# SparkFun_SOT23-DIP-Adapter-v10.net
KiCad netlist of a schematic drawn in EAGLE
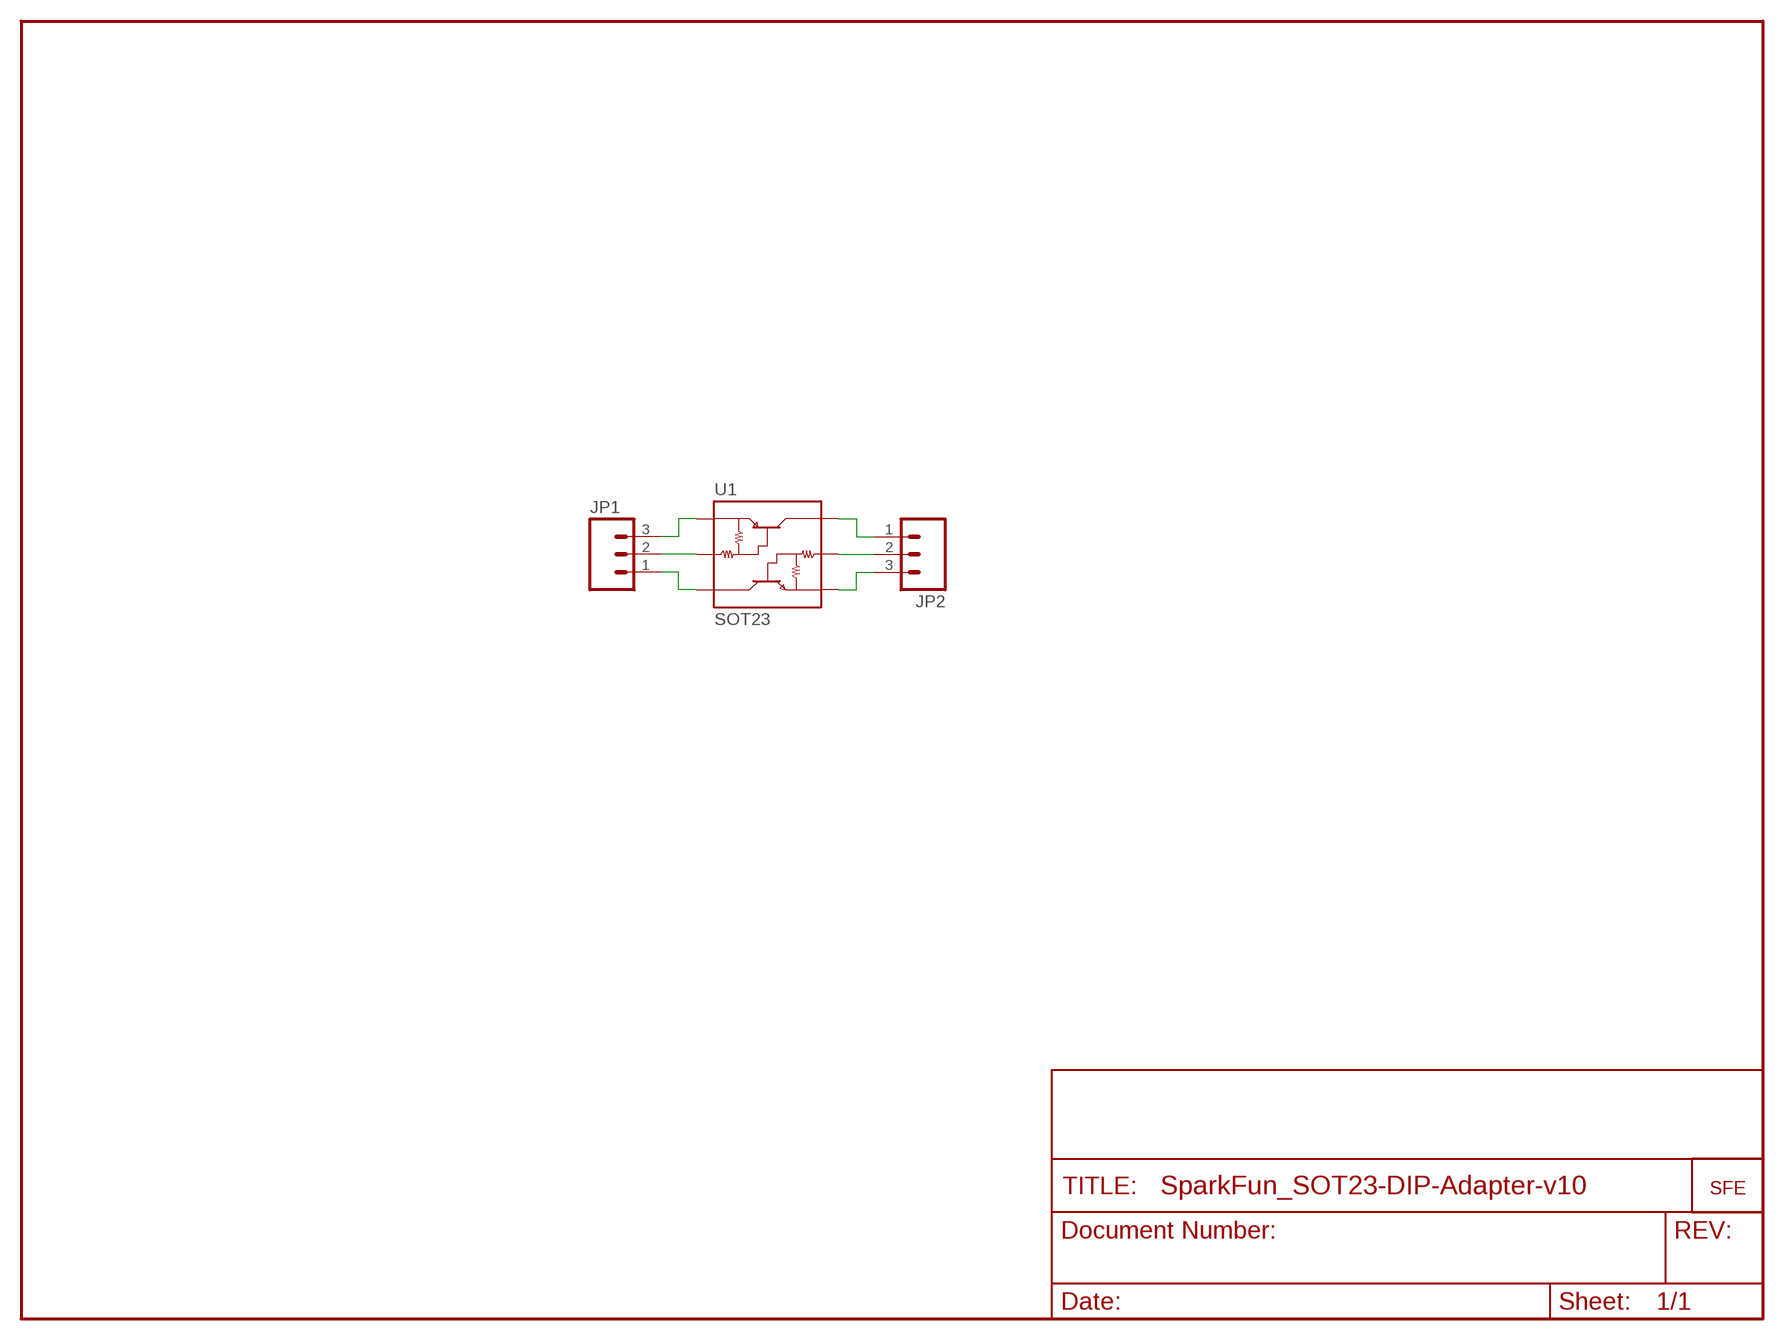
[diagram p0: schematic, sheet 1]

(export (version "E")
  (design (tool "Eeschema 10.0.6"))
  (components
    (comp (ref "JP1")
      (value "M03PTH")
      (footprint "eagle-import:1X03")
      (libsource (lib "eagle-import") (part "M03PTH"))
    )
    (comp (ref "JP2")
      (value "M03PTH")
      (footprint "eagle-import:1X03")
      (libsource (lib "eagle-import") (part "M03PTH"))
    )
    (comp (ref "U$1")
      (value "LOGO-SFESK")
      (footprint "eagle-import:SFE-LOGO-FLAME")
      (libsource (lib "eagle-import") (part "LOGO-SFESK"))
    )
    (comp (ref "U1")
      (value "SOT23")
      (footprint "eagle-import:SOT23-6")
      (libsource (lib "eagle-import") (part "XN04312SOT"))
    )
  )
  (nets
    (net (code "1") (name "Net-(U1-B1)") (class "Default")
      (node (ref "JP2") (pin "2") (pinfunction "2_2") (pintype "passive"))
      (node (ref "U1") (pin "5") (pinfunction "B1_5") (pintype "bidirectional"))
    )
    (net (code "2") (name "Net-(U1-B2)") (class "Default")
      (node (ref "JP1") (pin "2") (pinfunction "2_2") (pintype "passive"))
      (node (ref "U1") (pin "2") (pinfunction "B2_2") (pintype "bidirectional"))
    )
    (net (code "3") (name "Net-(U1-C1)") (class "Default")
      (node (ref "JP1") (pin "1") (pinfunction "1_1") (pintype "passive"))
      (node (ref "U1") (pin "1") (pinfunction "C1_1") (pintype "bidirectional"))
    )
    (net (code "4") (name "Net-(U1-C2)") (class "Default")
      (node (ref "JP2") (pin "1") (pinfunction "1_1") (pintype "passive"))
      (node (ref "U1") (pin "4") (pinfunction "C2_4") (pintype "bidirectional"))
    )
    (net (code "5") (name "Net-(U1-E1)") (class "Default")
      (node (ref "JP2") (pin "3") (pinfunction "3_3") (pintype "passive"))
      (node (ref "U1") (pin "6") (pinfunction "E1_6") (pintype "bidirectional"))
    )
    (net (code "6") (name "Net-(U1-E2)") (class "Default")
      (node (ref "JP1") (pin "3") (pinfunction "3_3") (pintype "passive"))
      (node (ref "U1") (pin "3") (pinfunction "E2_3") (pintype "bidirectional"))
    )
  )
)
